# elmo-adapter.net
KiCad netlist of a schematic drawn in Altium Designer
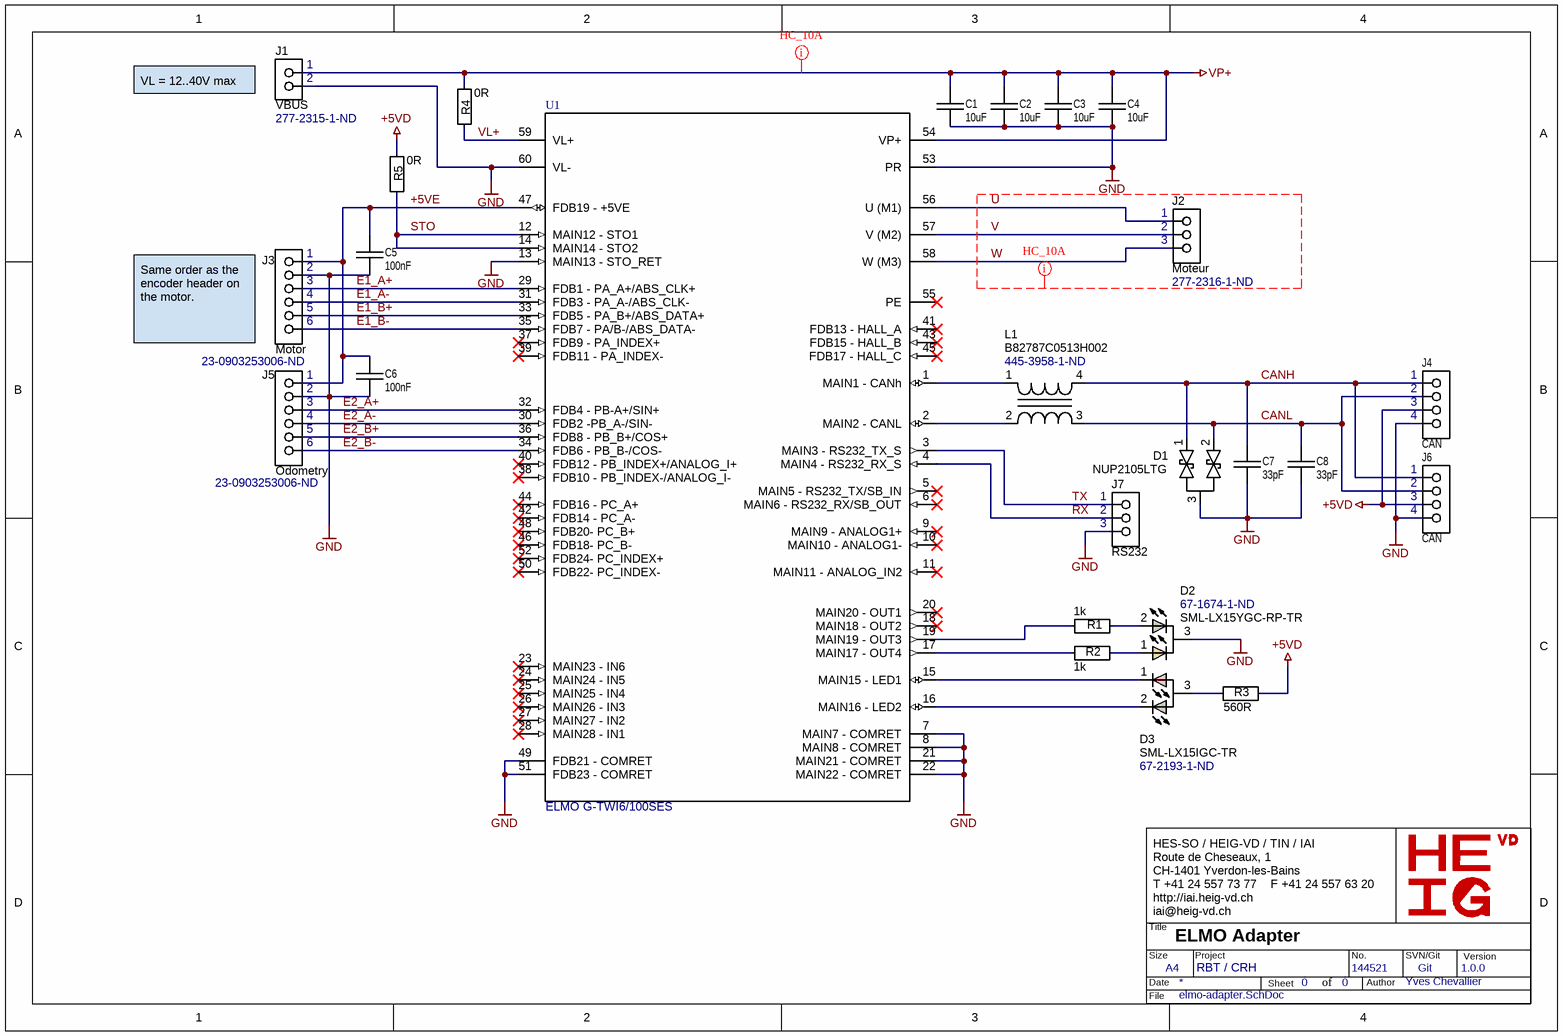
[diagram p0: elmo-adapter.SchDoc]

(export (version "E")
  (design (tool "Eeschema 10.0.6"))
  (components
    (comp (ref "C1")
      (value "10uF")
      (footprint "SM/C0805")
      (description "Chip Capacitor")
      (libsource (lib "kalios") (part "C"))
    )
    (comp (ref "C2")
      (value "10uF")
      (footprint "SM/C0805")
      (description "Chip Capacitor")
      (libsource (lib "kalios") (part "C"))
    )
    (comp (ref "C3")
      (value "10uF")
      (footprint "SM/C0805")
      (description "Chip Capacitor")
      (libsource (lib "kalios") (part "C"))
    )
    (comp (ref "C4")
      (value "10uF")
      (footprint "SM/C0805")
      (description "Chip Capacitor")
      (libsource (lib "kalios") (part "C"))
    )
    (comp (ref "C5")
      (value "100nF")
      (footprint "SM/C0805")
      (description "Chip Capacitor")
      (libsource (lib "kalios") (part "C"))
    )
    (comp (ref "C6")
      (value "100nF")
      (footprint "SM/C0805")
      (description "Chip Capacitor")
      (libsource (lib "kalios") (part "C"))
    )
    (comp (ref "C7")
      (value "33pF")
      (footprint "SM/C0603")
      (description "Chip Capacitor")
      (libsource (lib "kalios") (part "C"))
    )
    (comp (ref "C8")
      (value "33pF")
      (footprint "SM/C0603")
      (description "Chip Capacitor")
      (libsource (lib "kalios") (part "C"))
    )
    (comp (ref "D1")
      (value "NUP2105LTG")
      (footprint "SOT23-3")
      (libsource (lib "kalios") (part "NUP2105LTG"))
    )
    (comp (ref "D2")
      (value "SML-LX15YGC-RP-TR")
      (footprint "SOT23-3")
      (description "LED GREEN/YELLOW CLEAR SOT23 SMD")
      (fields (field (name "SUPPLIER PART NUMBER 1") "67-1674-1-ND"))
      (libsource (lib "kalios") (part "LED_SML-LX15YGC-RP-TR"))
    )
    (comp (ref "D3")
      (value "SML-LX15IGC-TR")
      (footprint "SOT23-3")
      (description "LED GREEN/RED CLEAR SOT23 SMD")
      (fields (field (name "SUPPLIER PART NUMBER 1") "67-2193-1-ND"))
      (libsource (lib "kalios") (part "LED_SML-LX15IGC-TR"))
    )
    (comp (ref "J1")
      (value "VBUS")
      (footprint "CONN 2POS 2.5mm 1778764")
      (fields (field (name "SUPPLIER PART NUMBER 1") "277-2315-1-ND"))
      (libsource (lib "kalios") (part "CONN 2"))
    )
    (comp (ref "J2")
      (value "Moteur")
      (footprint "CONN 3POS 2.5mm 1778777")
      (fields (field (name "SUPPLIER PART NUMBER 1") "277-2316-1-ND"))
      (libsource (lib "kalios") (part "CONN 3"))
    )
    (comp (ref "J3")
      (value "Motor")
      (footprint "CONN 6POS MOLEX 0903253006")
      (fields (field (name "SUPPLIER PART NUMBER 1") "23-0903253006-ND"))
      (libsource (lib "kalios") (part "CONN 6"))
    )
    (comp (ref "J4")
      (value "CAN")
      (footprint "CONN4 MICROMATCH TE/215079-4")
      (libsource (lib "kalios") (part "CONN 4"))
    )
    (comp (ref "J5")
      (value "Odometry")
      (footprint "CONN 6POS MOLEX 0903253006")
      (fields (field (name "SUPPLIER PART NUMBER 1") "23-0903253006-ND"))
      (libsource (lib "kalios") (part "CONN 6"))
    )
    (comp (ref "J6")
      (value "CAN")
      (footprint "CONN4 MICROMATCH TE/215079-4")
      (libsource (lib "kalios") (part "CONN 4"))
    )
    (comp (ref "J7") (value "RS232") (footprint "CONN/PIN3") (libsource (lib "kalios") (part "CONN 3")))
    (comp (ref "L1")
      (value "B82787C0513H002")
      (footprint "ACT45B")
      (description "CMC 51UH 200MA 2LN SMD AEC-Q200")
      (fields (field (name "SUPPLIER PART NUMBER 1") "445-3958-1-ND"))
      (libsource (lib "kalios") (part "L_B82787C0513H002"))
    )
    (comp (ref "R1")
      (value "1k")
      (footprint "SM/R0603")
      (description "Chip Resistor SMD")
      (libsource (lib "") (part "R_1"))
    )
    (comp (ref "R2")
      (value "1k")
      (footprint "SM/R0603")
      (description "Chip Resistor SMD")
      (libsource (lib "") (part "R_1"))
    )
    (comp (ref "R3")
      (value "560R")
      (footprint "SM/R0603")
      (description "Chip Resistor SMD")
      (libsource (lib "") (part "R_1"))
    )
    (comp (ref "R4")
      (value "0R")
      (footprint "SM/R0805")
      (description "Chip Resistor SMD")
      (libsource (lib "kalios") (part "R"))
    )
    (comp (ref "R5")
      (value "0R")
      (footprint "SM/R0805")
      (description "Chip Resistor SMD")
      (libsource (lib "kalios") (part "R"))
    )
    (comp (ref "U1")
      (value "ELMO G-TWI6/100SES")
      (footprint "ELMO G-TWI")
      (description "Gold Twitter G-TWITTER 6A/100VDC CAN ENC VL95")
      (libsource (lib "kalios") (part "ELMO G-TWI6/100SES"))
    )
  )
  (nets
    (net (code "1") (name "+5VD") (class "Default")
      (node (ref "J4") (pin "3") (pinfunction "3_3") (pintype "passive"))
      (node (ref "J6") (pin "3") (pinfunction "3_3") (pintype "passive"))
      (node (ref "R3") (pin "1") (pintype "passive"))
      (node (ref "R5") (pin "1") (pintype "passive"))
    )
    (net (code "2") (name "/+5VE") (class "Default")
      (node (ref "C5") (pin "1") (pintype "passive"))
      (node (ref "C6") (pin "1") (pintype "passive"))
      (node (ref "J3") (pin "1") (pinfunction "1_1") (pintype "passive"))
      (node (ref "J5") (pin "1") (pinfunction "1_1") (pintype "passive"))
      (node (ref "U1") (pin "47") (pinfunction "FDB19_-_+5VE_47") (pintype "bidirectional"))
    )
    (net (code "3") (name "/CANH") (class "Default")
      (node (ref "C7") (pin "1") (pintype "passive"))
      (node (ref "D1") (pin "1") (pinfunction "1_1") (pintype "passive"))
      (node (ref "J4") (pin "1") (pinfunction "1_1") (pintype "passive"))
      (node (ref "J6") (pin "1") (pinfunction "1_1") (pintype "passive"))
      (node (ref "L1") (pin "4") (pintype "passive"))
    )
    (net (code "4") (name "/CANL") (class "Default")
      (node (ref "C8") (pin "1") (pintype "passive"))
      (node (ref "D1") (pin "2") (pinfunction "21_2") (pintype "passive"))
      (node (ref "J4") (pin "2") (pinfunction "2_2") (pintype "passive"))
      (node (ref "J6") (pin "2") (pinfunction "2_2") (pintype "passive"))
      (node (ref "L1") (pin "3") (pintype "passive"))
    )
    (net (code "5") (name "/E1_A+") (class "Default")
      (node (ref "J3") (pin "3") (pinfunction "3_3") (pintype "passive"))
      (node (ref "U1") (pin "29") (pinfunction "FDB1_-_PA_A+/ABS_CLK+_29") (pintype "input"))
    )
    (net (code "6") (name "/E1_A-") (class "Default")
      (node (ref "J3") (pin "4") (pinfunction "4_4") (pintype "passive"))
      (node (ref "U1") (pin "31") (pinfunction "FDB3_-_PA_A-/ABS_CLK-_31") (pintype "input"))
    )
    (net (code "7") (name "/E1_B+") (class "Default")
      (node (ref "J3") (pin "5") (pinfunction "5_5") (pintype "passive"))
      (node (ref "U1") (pin "33") (pinfunction "FDB5_-_PA_B+/ABS_DATA+_33") (pintype "input"))
    )
    (net (code "8") (name "/E1_B-") (class "Default")
      (node (ref "J3") (pin "6") (pinfunction "6_6") (pintype "passive"))
      (node (ref "U1") (pin "35") (pinfunction "FDB7_-_PA/B-/ABS_DATA-_35") (pintype "input"))
    )
    (net (code "9") (name "/E2_A+") (class "Default")
      (node (ref "J5") (pin "3") (pinfunction "3_3") (pintype "passive"))
      (node (ref "U1") (pin "32") (pinfunction "FDB4_-_PB-A+/SIN+_32") (pintype "input"))
    )
    (net (code "10") (name "/E2_A-") (class "Default")
      (node (ref "J5") (pin "4") (pinfunction "4_4") (pintype "passive"))
      (node (ref "U1") (pin "30") (pinfunction "FDB2_-PB_A-/SIN-_30") (pintype "input"))
    )
    (net (code "11") (name "/E2_B+") (class "Default")
      (node (ref "J5") (pin "5") (pinfunction "5_5") (pintype "passive"))
      (node (ref "U1") (pin "36") (pinfunction "FDB8_-_PB_B+/COS+_36") (pintype "input"))
    )
    (net (code "12") (name "/E2_B-") (class "Default")
      (node (ref "J5") (pin "6") (pinfunction "6_6") (pintype "passive"))
      (node (ref "U1") (pin "34") (pinfunction "FDB6_-_PB_B-/COS-_34") (pintype "input"))
    )
    (net (code "13") (name "/RX") (class "Default")
      (node (ref "J7") (pin "2") (pinfunction "2_2") (pintype "passive"))
      (node (ref "U1") (pin "4") (pinfunction "MAIN4_-_RS232_RX_S_4") (pintype "input"))
    )
    (net (code "14") (name "/STO") (class "Default")
      (node (ref "R5") (pin "2") (pintype "passive"))
      (node (ref "U1") (pin "12") (pinfunction "MAIN12_-_STO1_12") (pintype "input"))
      (node (ref "U1") (pin "14") (pinfunction "MAIN14_-_STO2_14") (pintype "input"))
    )
    (net (code "15") (name "/TX") (class "Default")
      (node (ref "J7") (pin "1") (pinfunction "1_1") (pintype "passive"))
      (node (ref "U1") (pin "3") (pinfunction "MAIN3_-_RS232_TX_S_3") (pintype "output"))
    )
    (net (code "16") (name "/U") (class "Default")
      (node (ref "J2") (pin "1") (pinfunction "1_1") (pintype "passive"))
      (node (ref "U1") (pin "56") (pinfunction "U_(M1)_56") (pintype "passive"))
    )
    (net (code "17") (name "/V") (class "Default")
      (node (ref "J2") (pin "2") (pinfunction "2_2") (pintype "passive"))
      (node (ref "U1") (pin "57") (pinfunction "V_(M2)_57") (pintype "passive"))
    )
    (net (code "18") (name "/VL+") (class "Default")
      (node (ref "R4") (pin "2") (pintype "passive"))
      (node (ref "U1") (pin "59") (pinfunction "VL+_59") (pintype "passive"))
    )
    (net (code "19") (name "/W") (class "Default")
      (node (ref "J2") (pin "3") (pinfunction "3_3") (pintype "passive"))
      (node (ref "U1") (pin "58") (pinfunction "W_(M3)_58") (pintype "passive"))
    )
    (net (code "20") (name "GND") (class "Default")
      (node (ref "C1") (pin "2") (pintype "passive"))
      (node (ref "C2") (pin "2") (pintype "passive"))
      (node (ref "C3") (pin "2") (pintype "passive"))
      (node (ref "C4") (pin "2") (pintype "passive"))
      (node (ref "C5") (pin "2") (pintype "passive"))
      (node (ref "C6") (pin "2") (pintype "passive"))
      (node (ref "C7") (pin "2") (pintype "passive"))
      (node (ref "C8") (pin "2") (pintype "passive"))
      (node (ref "D1") (pin "3") (pinfunction "3_3") (pintype "passive"))
      (node (ref "D2") (pin "3") (pinfunction "ANODE_3") (pintype "passive"))
      (node (ref "J1") (pin "2") (pinfunction "2_2") (pintype "passive"))
      (node (ref "J3") (pin "2") (pinfunction "2_2") (pintype "passive"))
      (node (ref "J4") (pin "4") (pinfunction "4_4") (pintype "passive"))
      (node (ref "J5") (pin "2") (pinfunction "2_2") (pintype "passive"))
      (node (ref "J6") (pin "4") (pinfunction "4_4") (pintype "passive"))
      (node (ref "J7") (pin "3") (pinfunction "3_3") (pintype "passive"))
      (node (ref "U1") (pin "13") (pinfunction "MAIN13_-_STO_RET_13") (pintype "input"))
      (node (ref "U1") (pin "21") (pinfunction "MAIN21_-_COMRET_21") (pintype "passive"))
      (node (ref "U1") (pin "22") (pinfunction "MAIN22_-_COMRET_22") (pintype "passive"))
      (node (ref "U1") (pin "49") (pinfunction "FDB21_-_COMRET_49") (pintype "passive"))
      (node (ref "U1") (pin "51") (pinfunction "FDB23_-_COMRET_51") (pintype "passive"))
      (node (ref "U1") (pin "53") (pinfunction "PR_53") (pintype "passive"))
      (node (ref "U1") (pin "60") (pinfunction "VL-_60") (pintype "passive"))
      (node (ref "U1") (pin "7") (pinfunction "MAIN7_-_COMRET_7") (pintype "passive"))
      (node (ref "U1") (pin "8") (pinfunction "MAIN8_-_COMRET_8") (pintype "passive"))
    )
    (net (code "21") (name "Net-(D2-K_GREEN)") (class "Default")
      (node (ref "D2") (pin "2") (pinfunction "K_GREEN_2") (pintype "passive"))
      (node (ref "R1") (pin "1") (pintype "passive"))
    )
    (net (code "22") (name "Net-(D2-K_RED)") (class "Default")
      (node (ref "D2") (pin "1") (pinfunction "K_RED_1") (pintype "passive"))
      (node (ref "R2") (pin "1") (pintype "passive"))
    )
    (net (code "23") (name "Net-(D3-ANODE)") (class "Default")
      (node (ref "D3") (pin "3") (pinfunction "ANODE_3") (pintype "passive"))
      (node (ref "R3") (pin "2") (pintype "passive"))
    )
    (net (code "24") (name "Net-(D3-K_GREEN)") (class "Default")
      (node (ref "D3") (pin "2") (pinfunction "K_GREEN_2") (pintype "passive"))
      (node (ref "U1") (pin "16") (pinfunction "MAIN16_-_LED2_16") (pintype "bidirectional"))
    )
    (net (code "25") (name "Net-(D3-K_RED)") (class "Default")
      (node (ref "D3") (pin "1") (pinfunction "K_RED_1") (pintype "passive"))
      (node (ref "U1") (pin "15") (pinfunction "MAIN15_-_LED1_15") (pintype "bidirectional"))
    )
    (net (code "26") (name "Net-(U1-MAIN1_-_CANh)") (class "Default")
      (node (ref "L1") (pin "1") (pinfunction "1_1") (pintype "passive"))
      (node (ref "U1") (pin "1") (pinfunction "MAIN1_-_CANh_1") (pintype "bidirectional"))
    )
    (net (code "27") (name "Net-(U1-MAIN2_-_CANL)") (class "Default")
      (node (ref "L1") (pin "2") (pinfunction "2_2") (pintype "passive"))
      (node (ref "U1") (pin "2") (pinfunction "MAIN2_-_CANL_2") (pintype "bidirectional"))
    )
    (net (code "28") (name "Net-(U1-MAIN17_-_OUT4)") (class "Default")
      (node (ref "R2") (pin "2") (pintype "passive"))
      (node (ref "U1") (pin "17") (pinfunction "MAIN17_-_OUT4_17") (pintype "output"))
    )
    (net (code "29") (name "Net-(U1-MAIN19_-_OUT3)") (class "Default")
      (node (ref "R1") (pin "2") (pintype "passive"))
      (node (ref "U1") (pin "19") (pinfunction "MAIN19_-_OUT3_19") (pintype "output"))
    )
    (net (code "30") (name "VP+") (class "Default")
      (node (ref "C1") (pin "1") (pintype "passive"))
      (node (ref "C2") (pin "1") (pintype "passive"))
      (node (ref "C3") (pin "1") (pintype "passive"))
      (node (ref "C4") (pin "1") (pintype "passive"))
      (node (ref "J1") (pin "1") (pinfunction "1_1") (pintype "passive"))
      (node (ref "R4") (pin "1") (pintype "passive"))
      (node (ref "U1") (pin "54") (pinfunction "VP+_54") (pintype "passive"))
    )
    (net (code "31") (name "unconnected-(U1-FDB9_-_PA_INDEX+-Pad37)") (class "Default")
      (node (ref "U1") (pin "37") (pinfunction "FDB9_-_PA_INDEX+_37") (pintype "input+no_connect"))
    )
    (net (code "32") (name "unconnected-(U1-FDB10_-_PB_INDEX-{slash}ANALOG_I--Pad38)") (class "Default")
      (node (ref "U1") (pin "38") (pinfunction "FDB10_-_PB_INDEX-/ANALOG_I-_38") (pintype "input+no_connect"))
    )
    (net (code "33") (name "unconnected-(U1-FDB11_-_PA_INDEX--Pad39)") (class "Default")
      (node (ref "U1") (pin "39") (pinfunction "FDB11_-_PA_INDEX-_39") (pintype "input+no_connect"))
    )
    (net (code "34") (name "unconnected-(U1-FDB12_-_PB_INDEX+{slash}ANALOG_I+-Pad40)") (class "Default")
      (node (ref "U1") (pin "40") (pinfunction "FDB12_-_PB_INDEX+/ANALOG_I+_40") (pintype "input+no_connect"))
    )
    (net (code "35") (name "unconnected-(U1-FDB13_-_HALL_A-Pad41)") (class "Default")
      (node (ref "U1") (pin "41") (pinfunction "FDB13_-_HALL_A_41") (pintype "input+no_connect"))
    )
    (net (code "36") (name "unconnected-(U1-FDB14_-_PC_A--Pad42)") (class "Default")
      (node (ref "U1") (pin "42") (pinfunction "FDB14_-_PC_A-_42") (pintype "input+no_connect"))
    )
    (net (code "37") (name "unconnected-(U1-FDB15_-_HALL_B-Pad43)") (class "Default")
      (node (ref "U1") (pin "43") (pinfunction "FDB15_-_HALL_B_43") (pintype "input+no_connect"))
    )
    (net (code "38") (name "unconnected-(U1-FDB16_-_PC_A+-Pad44)") (class "Default")
      (node (ref "U1") (pin "44") (pinfunction "FDB16_-_PC_A+_44") (pintype "input+no_connect"))
    )
    (net (code "39") (name "unconnected-(U1-FDB17_-_HALL_C-Pad45)") (class "Default")
      (node (ref "U1") (pin "45") (pinfunction "FDB17_-_HALL_C_45") (pintype "input+no_connect"))
    )
    (net (code "40") (name "unconnected-(U1-FDB18-_PC_B--Pad46)") (class "Default")
      (node (ref "U1") (pin "46") (pinfunction "FDB18-_PC_B-_46") (pintype "input+no_connect"))
    )
    (net (code "41") (name "unconnected-(U1-FDB20-_PC_B+-Pad48)") (class "Default")
      (node (ref "U1") (pin "48") (pinfunction "FDB20-_PC_B+_48") (pintype "input+no_connect"))
    )
    (net (code "42") (name "unconnected-(U1-FDB22-_PC_INDEX--Pad50)") (class "Default")
      (node (ref "U1") (pin "50") (pinfunction "FDB22-_PC_INDEX-_50") (pintype "input+no_connect"))
    )
    (net (code "43") (name "unconnected-(U1-FDB24-_PC_INDEX+-Pad52)") (class "Default")
      (node (ref "U1") (pin "52") (pinfunction "FDB24-_PC_INDEX+_52") (pintype "input+no_connect"))
    )
    (net (code "44") (name "unconnected-(U1-MAIN5_-_RS232_TX{slash}SB_IN-Pad5)") (class "Default")
      (node (ref "U1") (pin "5") (pinfunction "MAIN5_-_RS232_TX/SB_IN_5") (pintype "output+no_connect"))
    )
    (net (code "45") (name "unconnected-(U1-MAIN6_-_RS232_RX{slash}SB_OUT-Pad6)") (class "Default")
      (node (ref "U1") (pin "6") (pinfunction "MAIN6_-_RS232_RX/SB_OUT_6") (pintype "input+no_connect"))
    )
    (net (code "46") (name "unconnected-(U1-MAIN9_-_ANALOG1+-Pad9)") (class "Default")
      (node (ref "U1") (pin "9") (pinfunction "MAIN9_-_ANALOG1+_9") (pintype "input+no_connect"))
    )
    (net (code "47") (name "unconnected-(U1-MAIN10_-_ANALOG1--Pad10)") (class "Default")
      (node (ref "U1") (pin "10") (pinfunction "MAIN10_-_ANALOG1-_10") (pintype "input+no_connect"))
    )
    (net (code "48") (name "unconnected-(U1-MAIN11_-_ANALOG_IN2-Pad11)") (class "Default")
      (node (ref "U1") (pin "11") (pinfunction "MAIN11_-_ANALOG_IN2_11") (pintype "input+no_connect"))
    )
    (net (code "49") (name "unconnected-(U1-MAIN18_-_OUT2-Pad18)") (class "Default")
      (node (ref "U1") (pin "18") (pinfunction "MAIN18_-_OUT2_18") (pintype "output+no_connect"))
    )
    (net (code "50") (name "unconnected-(U1-MAIN20_-_OUT1-Pad20)") (class "Default")
      (node (ref "U1") (pin "20") (pinfunction "MAIN20_-_OUT1_20") (pintype "output+no_connect"))
    )
    (net (code "51") (name "unconnected-(U1-MAIN23_-_IN6-Pad23)") (class "Default")
      (node (ref "U1") (pin "23") (pinfunction "MAIN23_-_IN6_23") (pintype "input+no_connect"))
    )
    (net (code "52") (name "unconnected-(U1-MAIN24_-_IN5-Pad24)") (class "Default")
      (node (ref "U1") (pin "24") (pinfunction "MAIN24_-_IN5_24") (pintype "input+no_connect"))
    )
    (net (code "53") (name "unconnected-(U1-MAIN25_-_IN4-Pad25)") (class "Default")
      (node (ref "U1") (pin "25") (pinfunction "MAIN25_-_IN4_25") (pintype "input+no_connect"))
    )
    (net (code "54") (name "unconnected-(U1-MAIN26_-_IN3-Pad26)") (class "Default")
      (node (ref "U1") (pin "26") (pinfunction "MAIN26_-_IN3_26") (pintype "input+no_connect"))
    )
    (net (code "55") (name "unconnected-(U1-MAIN27_-_IN2-Pad27)") (class "Default")
      (node (ref "U1") (pin "27") (pinfunction "MAIN27_-_IN2_27") (pintype "input+no_connect"))
    )
    (net (code "56") (name "unconnected-(U1-MAIN28_-_IN1-Pad28)") (class "Default")
      (node (ref "U1") (pin "28") (pinfunction "MAIN28_-_IN1_28") (pintype "input+no_connect"))
    )
    (net (code "57") (name "unconnected-(U1-PE-Pad55)") (class "Default")
      (node (ref "U1") (pin "55") (pinfunction "PE_55") (pintype "passive+no_connect"))
    )
  )
)
